# Memory.net
KiCad netlist of a schematic drawn in Altium Designer
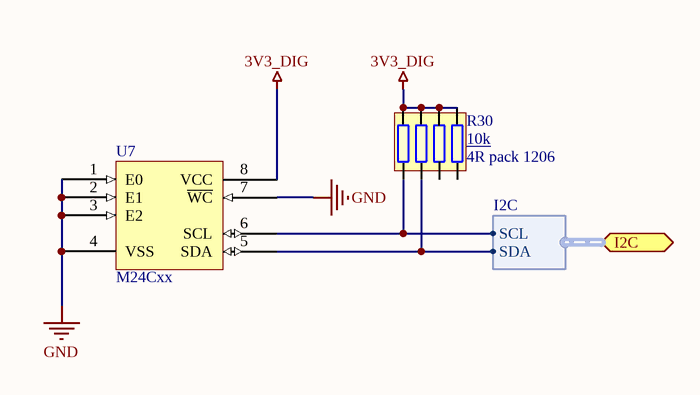
[diagram p0: Memory.SchDoc]

(export (version "E")
  (design (tool "Eeschema 10.0.6"))
  (components
    (comp (ref "R30")
      (value "10k")
      (footprint "4R pack 1206")
      (description "4 resistor pack array")
      (libsource (lib "_RLC") (part "Rres_pack_4"))
    )
    (comp (ref "U7")
      (value "M24Cxx")
      (footprint "SOIC-8_M")
      (description "M24Cxx flash memory")
      (libsource (lib "_Microcircuits") (part "M24Cxx"))
    )
  )
  (nets
    (net (code "3") (name "3V3_DIG") (class "Default")
      (node (ref "R30") (pin "5") (pinfunction "5_5") (pintype "passive"))
      (node (ref "R30") (pin "6") (pinfunction "6_6") (pintype "passive"))
      (node (ref "R30") (pin "7") (pinfunction "7_7") (pintype "passive"))
      (node (ref "R30") (pin "8") (pinfunction "8_8") (pintype "passive"))
      (node (ref "U7") (pin "8") (pinfunction "VCC_8") (pintype "power_in"))
    )
    (net (code "4") (name "GND") (class "Default")
      (node (ref "U7") (pin "1") (pinfunction "E0_1") (pintype "input"))
      (node (ref "U7") (pin "2") (pinfunction "E1_2") (pintype "input"))
      (node (ref "U7") (pin "3") (pinfunction "E2_3") (pintype "input"))
      (node (ref "U7") (pin "4") (pinfunction "VSS_4") (pintype "power_in"))
      (node (ref "U7") (pin "7") (pinfunction "WC_7") (pintype "input"))
    )
    (net (code "5") (name "Net-(U7-SCL)") (class "Default")
      (node (ref "R30") (pin "1") (pinfunction "1_1") (pintype "passive"))
      (node (ref "U7") (pin "6") (pinfunction "SCL_6") (pintype "bidirectional"))
    )
    (net (code "6") (name "Net-(U7-SDA)") (class "Default")
      (node (ref "R30") (pin "2") (pinfunction "2_2") (pintype "passive"))
      (node (ref "U7") (pin "5") (pinfunction "SDA_5") (pintype "bidirectional"))
    )
    (net (code "7") (name "unconnected-(R30-Pad3)") (class "Default")
      (node (ref "R30") (pin "3") (pinfunction "3_3") (pintype "passive"))
    )
    (net (code "8") (name "unconnected-(R30-Pad4)") (class "Default")
      (node (ref "R30") (pin "4") (pinfunction "4_4") (pintype "passive"))
    )
  )
)
